# senseBox-MCU_v10.net
KiCad netlist of a schematic drawn in EAGLE
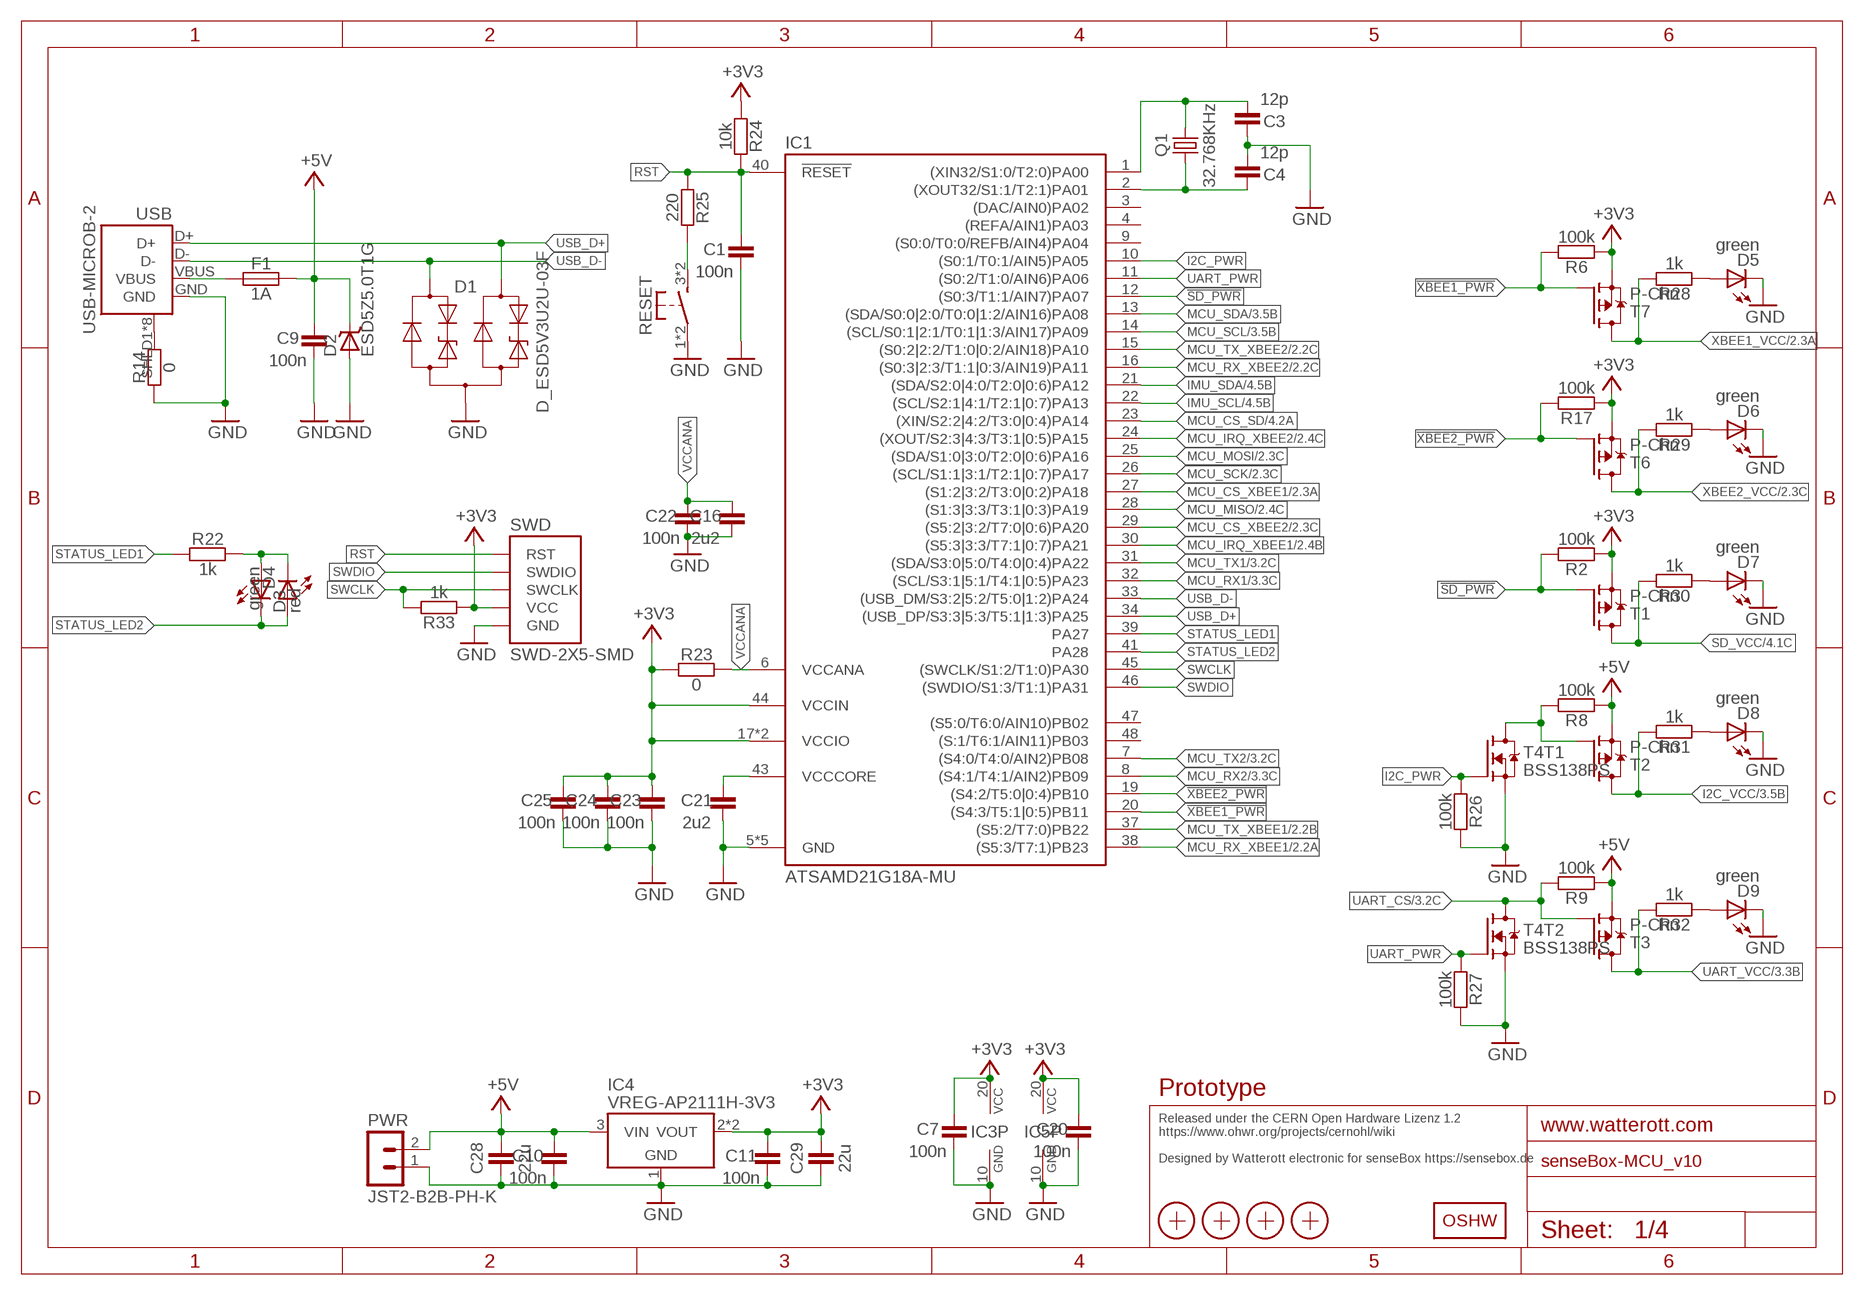
[diagram p0: schematic, sheet 1]
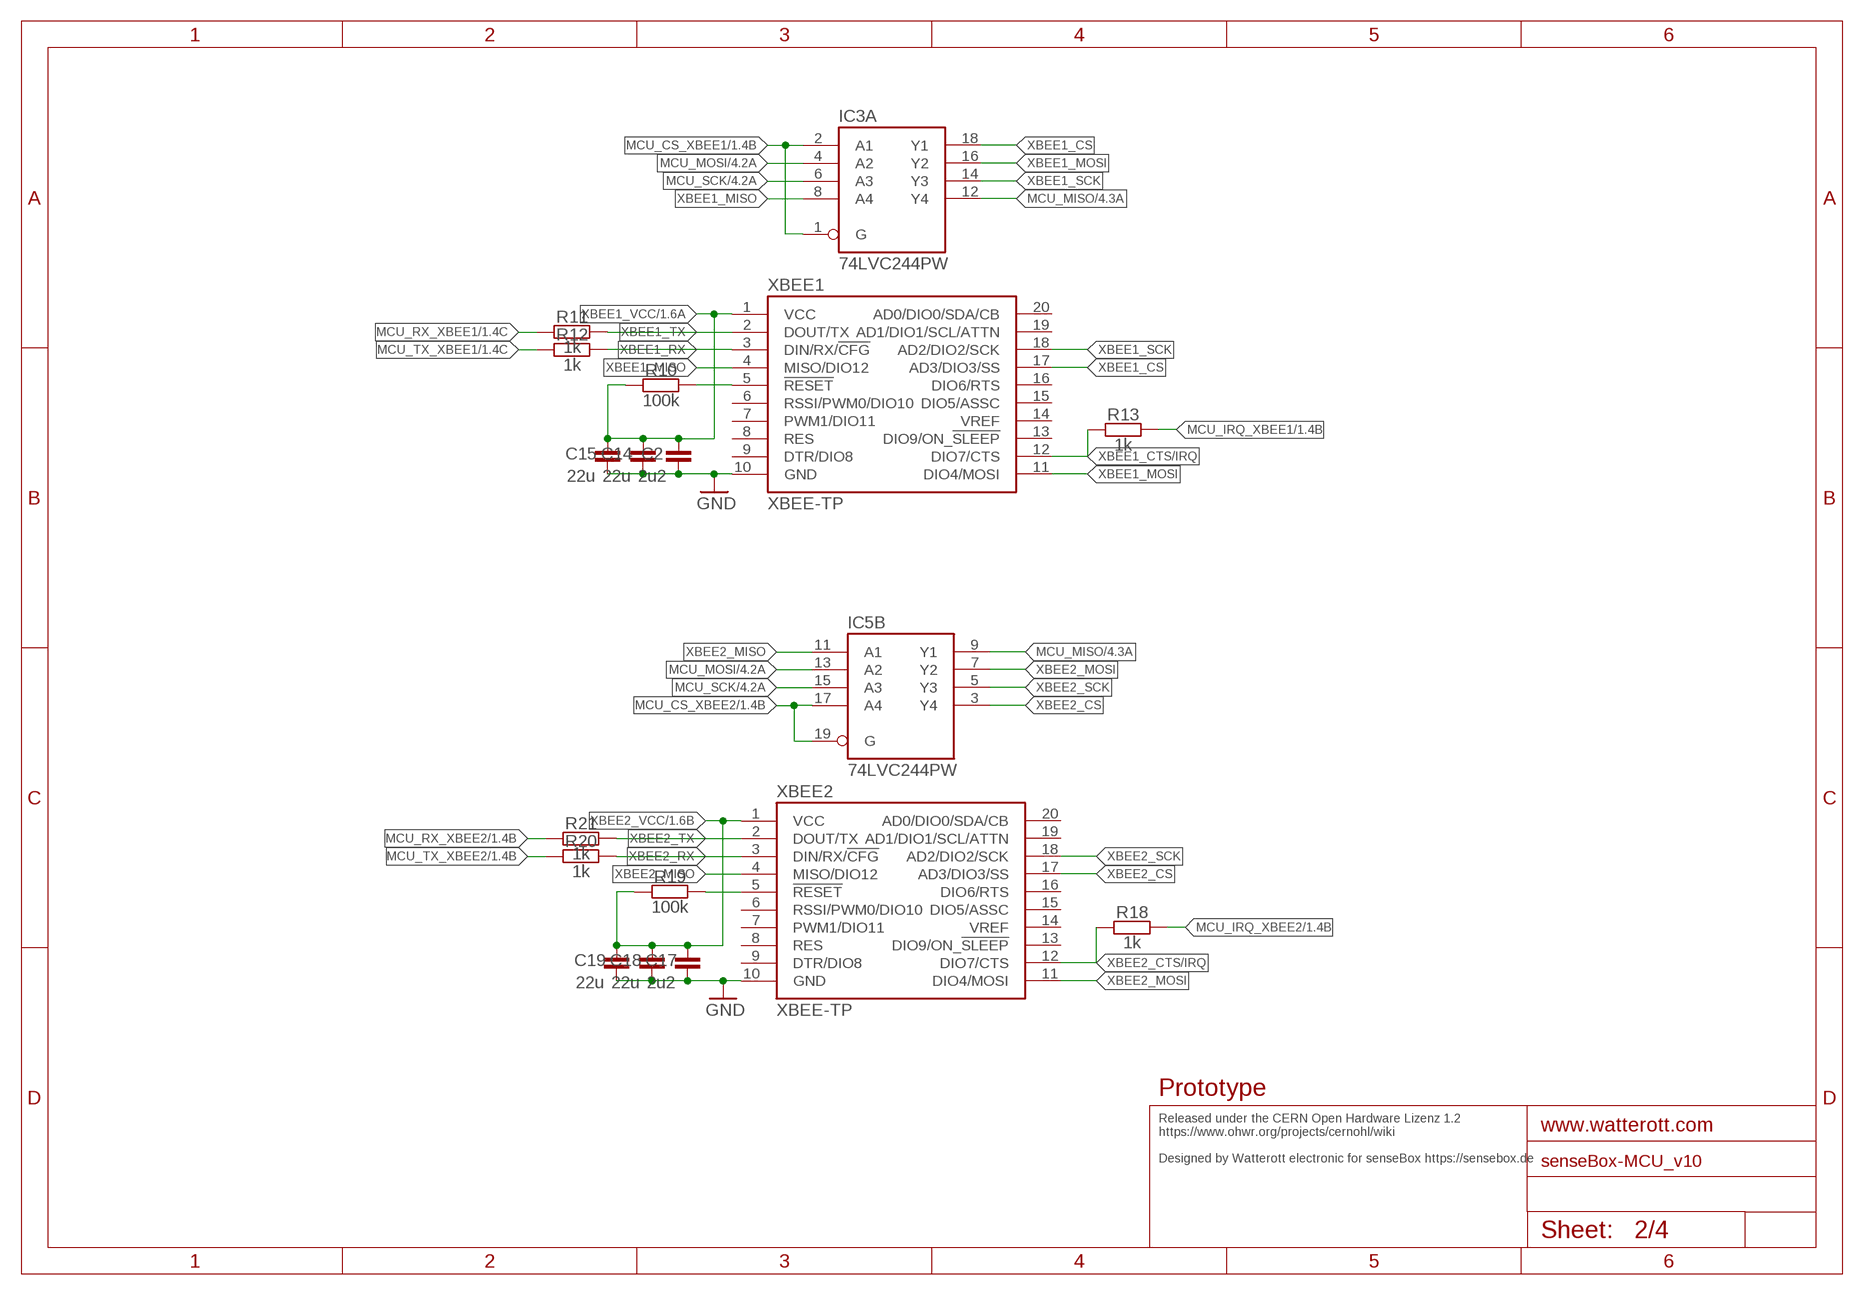
[diagram p1: schematic, sheet 2]
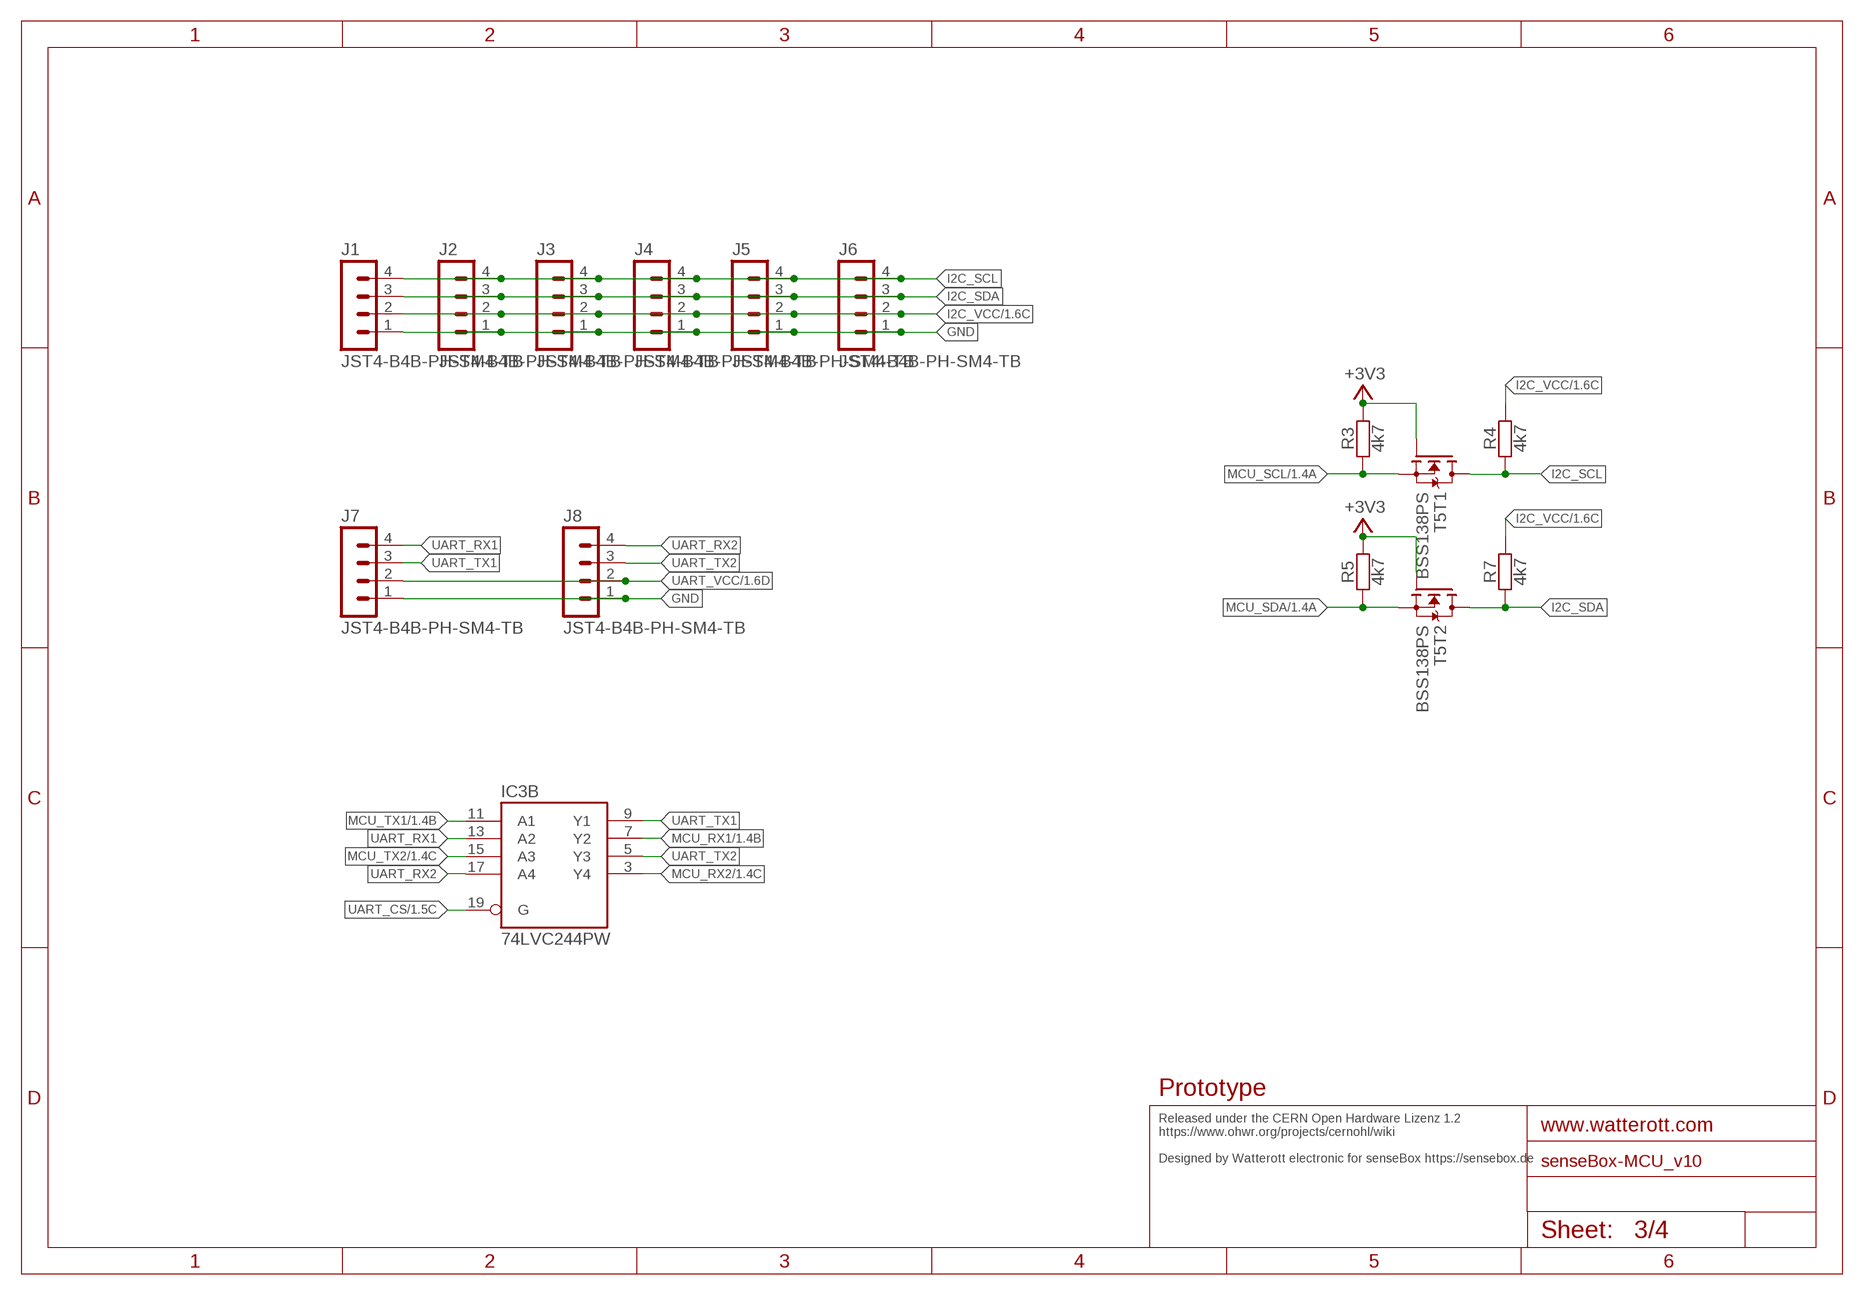
[diagram p2: schematic, sheet 3]
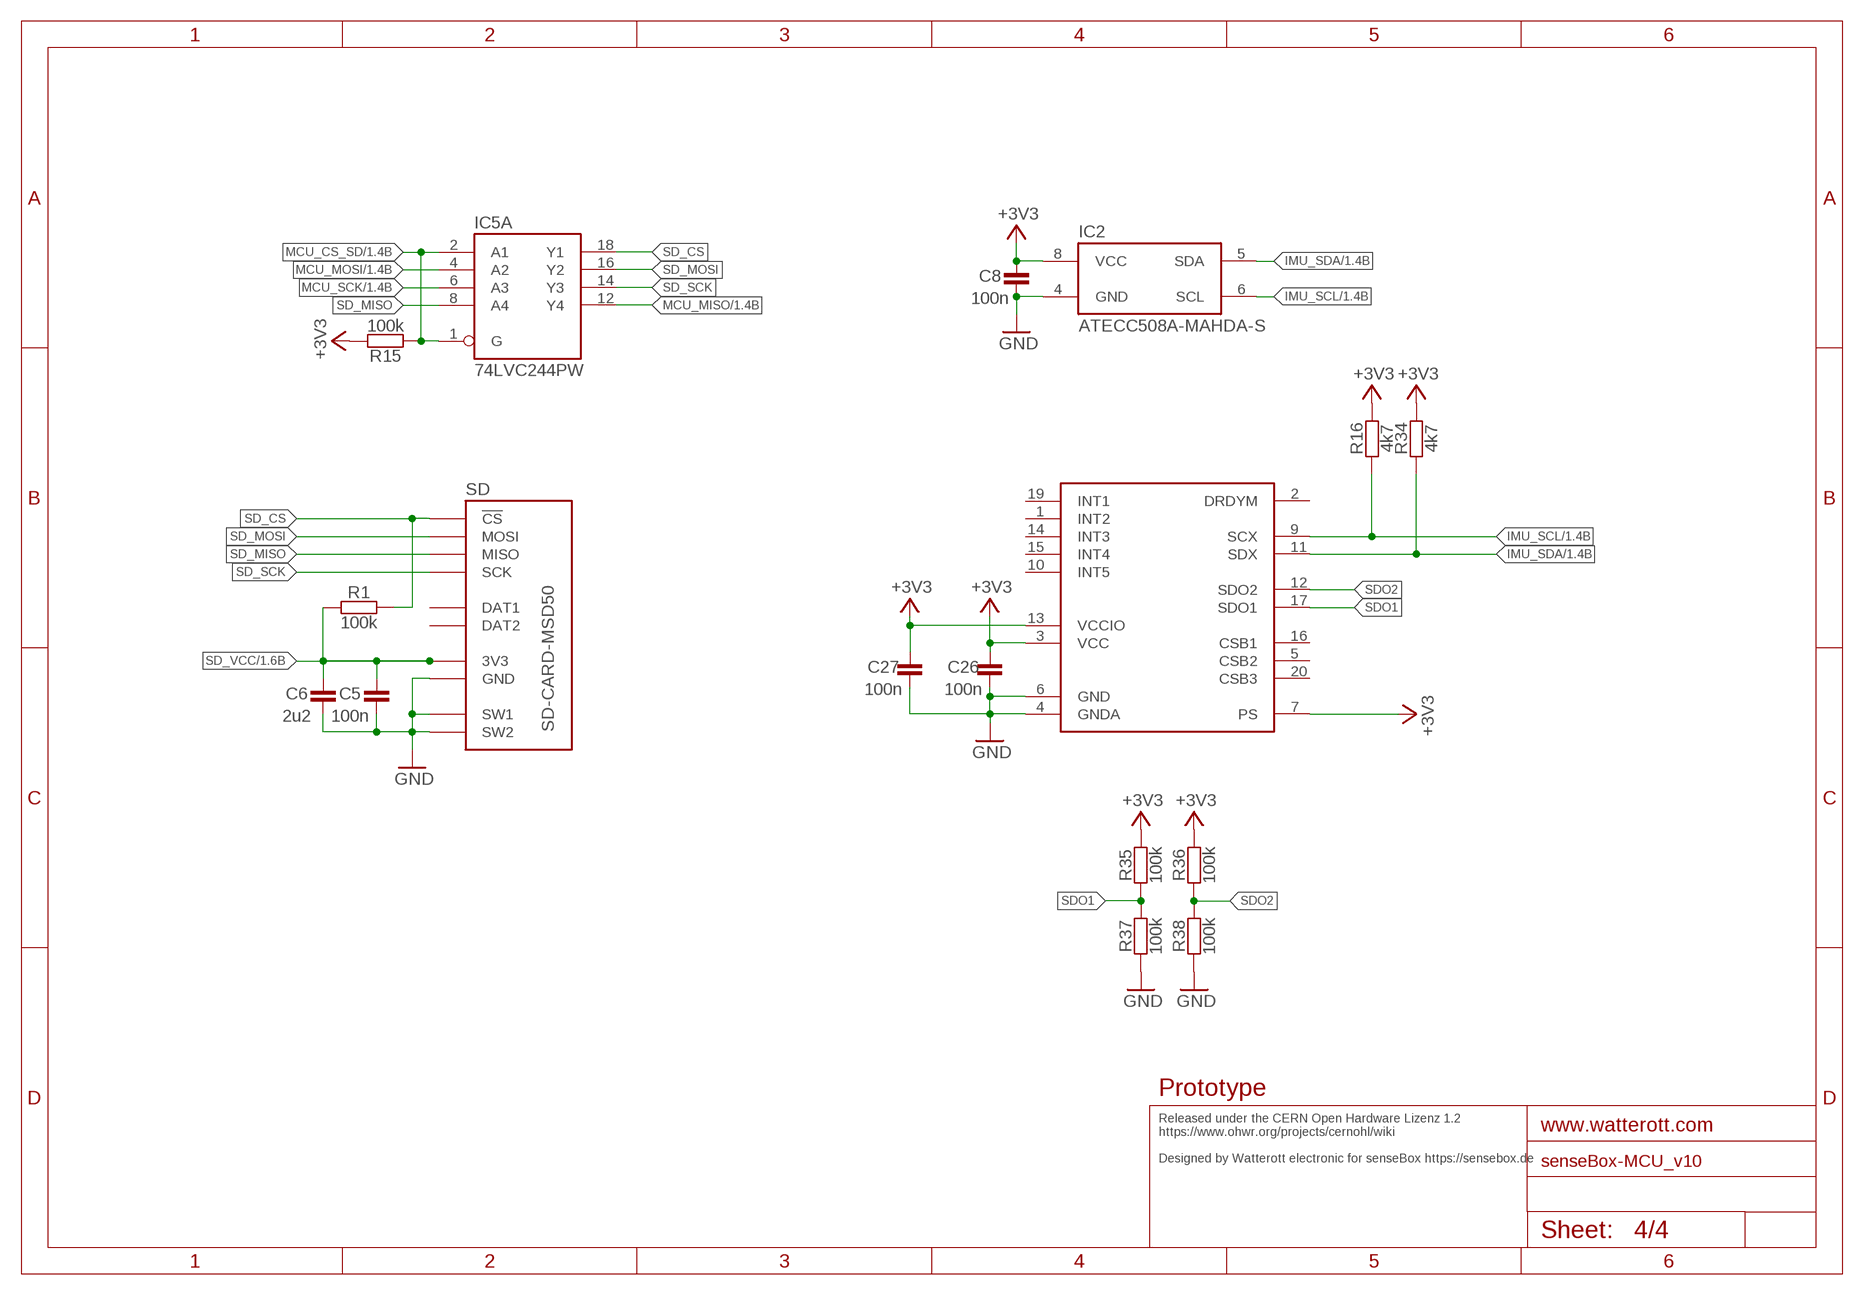
[diagram p3: schematic, sheet 4]

(export (version "E")
  (design (tool "Eeschema 10.0.6"))
  (components
    (comp (ref "C2")
      (value "2u2")
      (footprint "eagle-import:C0402")
      (libsource (lib "eagle-import") (part "CAPACITOR-0402"))
    )
    (comp (ref "C14")
      (value "22u")
      (footprint "eagle-import:C0805")
      (libsource (lib "eagle-import") (part "CAPACITOR-0805"))
    )
    (comp (ref "C15")
      (value "22u")
      (footprint "eagle-import:C0805")
      (libsource (lib "eagle-import") (part "CAPACITOR-0805"))
    )
    (comp (ref "C17")
      (value "2u2")
      (footprint "eagle-import:C0402")
      (libsource (lib "eagle-import") (part "CAPACITOR-0402"))
    )
    (comp (ref "C18")
      (value "22u")
      (footprint "eagle-import:C0805")
      (libsource (lib "eagle-import") (part "CAPACITOR-0805"))
    )
    (comp (ref "C19")
      (value "22u")
      (footprint "eagle-import:C0805")
      (libsource (lib "eagle-import") (part "CAPACITOR-0805"))
    )
    (comp (ref "IC3")
      (value "74LVC244PW")
      (footprint "eagle-import:TSSOP20")
      (libsource (lib "eagle-import") (part "74244PWLVC"))
    )
    (comp (ref "IC5")
      (value "74LVC244PW")
      (footprint "eagle-import:TSSOP20")
      (libsource (lib "eagle-import") (part "74244PWLVC"))
    )
    (comp (ref "R10")
      (value "100k")
      (footprint "eagle-import:C0402")
      (libsource (lib "eagle-import") (part "RESISTOR-0402"))
    )
    (comp (ref "R11")
      (value "1k")
      (footprint "eagle-import:C0402")
      (libsource (lib "eagle-import") (part "RESISTOR-0402"))
    )
    (comp (ref "R12")
      (value "1k")
      (footprint "eagle-import:C0402")
      (libsource (lib "eagle-import") (part "RESISTOR-0402"))
    )
    (comp (ref "R13")
      (value "1k")
      (footprint "eagle-import:C0402")
      (libsource (lib "eagle-import") (part "RESISTOR-0402"))
    )
    (comp (ref "R18")
      (value "1k")
      (footprint "eagle-import:C0402")
      (libsource (lib "eagle-import") (part "RESISTOR-0402"))
    )
    (comp (ref "R19")
      (value "100k")
      (footprint "eagle-import:C0402")
      (libsource (lib "eagle-import") (part "RESISTOR-0402"))
    )
    (comp (ref "R20")
      (value "1k")
      (footprint "eagle-import:C0402")
      (libsource (lib "eagle-import") (part "RESISTOR-0402"))
    )
    (comp (ref "R21")
      (value "1k")
      (footprint "eagle-import:C0402")
      (libsource (lib "eagle-import") (part "RESISTOR-0402"))
    )
    (comp (ref "XBEE1")
      (value "XBEE-TP")
      (footprint "eagle-import:XBEE_TP")
      (libsource (lib "eagle-import") (part "XBEE-TP"))
    )
    (comp (ref "XBEE2")
      (value "XBEE-TP")
      (footprint "eagle-import:XBEE_TP")
      (libsource (lib "eagle-import") (part "XBEE-TP"))
    )
    (comp (ref "C5")
      (value "100n")
      (footprint "eagle-import:C0402")
      (libsource (lib "eagle-import") (part "CAPACITOR-0402"))
    )
    (comp (ref "C6")
      (value "2u2")
      (footprint "eagle-import:C0402")
      (libsource (lib "eagle-import") (part "CAPACITOR-0402"))
    )
    (comp (ref "C8")
      (value "100n")
      (footprint "eagle-import:C0402")
      (libsource (lib "eagle-import") (part "CAPACITOR-0402"))
    )
    (comp (ref "C26")
      (value "100n")
      (footprint "eagle-import:C0402")
      (libsource (lib "eagle-import") (part "CAPACITOR-0402"))
    )
    (comp (ref "C27")
      (value "100n")
      (footprint "eagle-import:C0402")
      (libsource (lib "eagle-import") (part "CAPACITOR-0402"))
    )
    (comp (ref "IC2")
      (value "ATECC508A-MAHDA-S")
      (footprint "eagle-import:UDFN8")
      (libsource (lib "eagle-import") (part "ATECC508A-MAHDA-S"))
    )
    (comp (ref "R1")
      (value "100k")
      (footprint "eagle-import:C0402")
      (libsource (lib "eagle-import") (part "RESISTOR-0402"))
    )
    (comp (ref "R15")
      (value "100k")
      (footprint "eagle-import:C0402")
      (libsource (lib "eagle-import") (part "RESISTOR-0402"))
    )
    (comp (ref "R16")
      (value "4k7")
      (footprint "eagle-import:C0402")
      (libsource (lib "eagle-import") (part "RESISTOR-0402"))
    )
    (comp (ref "R34")
      (value "4k7")
      (footprint "eagle-import:C0402")
      (libsource (lib "eagle-import") (part "RESISTOR-0402"))
    )
    (comp (ref "R35")
      (value "100k")
      (footprint "eagle-import:C0402")
      (libsource (lib "eagle-import") (part "RESISTOR-0402"))
    )
    (comp (ref "R36")
      (value "100k")
      (footprint "eagle-import:C0402")
      (libsource (lib "eagle-import") (part "RESISTOR-0402"))
    )
    (comp (ref "R37")
      (value "100k")
      (footprint "eagle-import:C0402")
      (libsource (lib "eagle-import") (part "RESISTOR-0402"))
    )
    (comp (ref "R38")
      (value "100k")
      (footprint "eagle-import:C0402")
      (libsource (lib "eagle-import") (part "RESISTOR-0402"))
    )
    (comp (ref "SD")
      (value "SD-CARD-MSD50")
      (footprint "eagle-import:SD_5031821853")
      (libsource (lib "eagle-import") (part "SD-CARD-MSD50"))
    )
    (comp (ref "U1")
      (value "BMX055")
      (footprint "eagle-import:BMX055")
      (libsource (lib "eagle-import") (part "BMX055"))
    )
    (comp (ref "C1")
      (value "100n")
      (footprint "eagle-import:C0402")
      (libsource (lib "eagle-import") (part "CAPACITOR-0402"))
    )
    (comp (ref "C3")
      (value "12p")
      (footprint "eagle-import:C0402")
      (libsource (lib "eagle-import") (part "CAPACITOR-0402"))
    )
    (comp (ref "C4")
      (value "12p")
      (footprint "eagle-import:C0402")
      (libsource (lib "eagle-import") (part "CAPACITOR-0402"))
    )
    (comp (ref "C7")
      (value "100n")
      (footprint "eagle-import:C0402")
      (libsource (lib "eagle-import") (part "CAPACITOR-0402"))
    )
    (comp (ref "C9")
      (value "100n")
      (footprint "eagle-import:C0402")
      (libsource (lib "eagle-import") (part "CAPACITOR-0402"))
    )
    (comp (ref "C10")
      (value "100n")
      (footprint "eagle-import:C0402")
      (libsource (lib "eagle-import") (part "CAPACITOR-0402"))
    )
    (comp (ref "C11")
      (value "100n")
      (footprint "eagle-import:C0402")
      (libsource (lib "eagle-import") (part "CAPACITOR-0402"))
    )
    (comp (ref "C16")
      (value "2u2")
      (footprint "eagle-import:C0402")
      (libsource (lib "eagle-import") (part "CAPACITOR-0402"))
    )
    (comp (ref "C20")
      (value "100n")
      (footprint "eagle-import:C0402")
      (libsource (lib "eagle-import") (part "CAPACITOR-0402"))
    )
    (comp (ref "C21")
      (value "2u2")
      (footprint "eagle-import:C0402")
      (libsource (lib "eagle-import") (part "CAPACITOR-0402"))
    )
    (comp (ref "C22")
      (value "100n")
      (footprint "eagle-import:C0402")
      (libsource (lib "eagle-import") (part "CAPACITOR-0402"))
    )
    (comp (ref "C23")
      (value "100n")
      (footprint "eagle-import:C0402")
      (libsource (lib "eagle-import") (part "CAPACITOR-0402"))
    )
    (comp (ref "C24")
      (value "100n")
      (footprint "eagle-import:C0402")
      (libsource (lib "eagle-import") (part "CAPACITOR-0402"))
    )
    (comp (ref "C25")
      (value "100n")
      (footprint "eagle-import:C0402")
      (libsource (lib "eagle-import") (part "CAPACITOR-0402"))
    )
    (comp (ref "C28")
      (value "22u")
      (footprint "eagle-import:C0805")
      (libsource (lib "eagle-import") (part "CAPACITOR-0805"))
    )
    (comp (ref "C29")
      (value "22u")
      (footprint "eagle-import:C0805")
      (libsource (lib "eagle-import") (part "CAPACITOR-0805"))
    )
    (comp (ref "D1")
      (value "D_ESD5V3U2U-03F")
      (footprint "eagle-import:SOT723")
      (libsource (lib "eagle-import") (part "D_ESD5V3U2U-03F"))
    )
    (comp (ref "D2")
      (value "ESD5Z5.0T1G")
      (footprint "eagle-import:SOD523")
      (libsource (lib "eagle-import") (part "D_TVS-SOD523"))
    )
    (comp (ref "D3")
      (value "red")
      (footprint "eagle-import:C0603")
      (libsource (lib "eagle-import") (part "LED-0603"))
    )
    (comp (ref "D4")
      (value "green")
      (footprint "eagle-import:C0603")
      (libsource (lib "eagle-import") (part "LED-0603"))
    )
    (comp (ref "D5")
      (value "green")
      (footprint "eagle-import:C0603")
      (libsource (lib "eagle-import") (part "LED-0603"))
    )
    (comp (ref "D6")
      (value "green")
      (footprint "eagle-import:C0603")
      (libsource (lib "eagle-import") (part "LED-0603"))
    )
    (comp (ref "D7")
      (value "green")
      (footprint "eagle-import:C0603")
      (libsource (lib "eagle-import") (part "LED-0603"))
    )
    (comp (ref "D8")
      (value "green")
      (footprint "eagle-import:C0603")
      (libsource (lib "eagle-import") (part "LED-0603"))
    )
    (comp (ref "D9")
      (value "green")
      (footprint "eagle-import:C0603")
      (libsource (lib "eagle-import") (part "LED-0603"))
    )
    (comp (ref "F1")
      (value "1A")
      (footprint "eagle-import:C0805")
      (libsource (lib "eagle-import") (part "FUSE-0805"))
    )
    (comp (ref "IC1")
      (value "ATSAMD21G18A-MU")
      (footprint "eagle-import:QFN48-PAD")
      (libsource (lib "eagle-import") (part "ATSAMD21G18A-MU"))
    )
    (comp (ref "IC4")
      (value "VREG-AP2111H-3V3")
      (footprint "eagle-import:SOT223")
      (libsource (lib "eagle-import") (part "VREG-TS1117CW-3V3"))
    )
    (comp (ref "LOGO2")
      (value "OSHW_LOGOX0070")
      (footprint "eagle-import:OSHW_6X70")
      (libsource (lib "eagle-import") (part "OSHW_LOGOX0070"))
    )
    (comp (ref "PWR")
      (value "JST2-B2B-PH-K")
      (footprint "eagle-import:JST_B2B-PH-K")
      (libsource (lib "eagle-import") (part "JST2-B2B-PH-K"))
    )
    (comp (ref "Q1")
      (value "32.768KHz")
      (footprint "eagle-import:CRYSTAL_ZM315")
      (libsource (lib "eagle-import") (part "CRYSTAL-ZM315"))
    )
    (comp (ref "R2")
      (value "100k")
      (footprint "eagle-import:C0402")
      (libsource (lib "eagle-import") (part "RESISTOR-0402"))
    )
    (comp (ref "R6")
      (value "100k")
      (footprint "eagle-import:C0402")
      (libsource (lib "eagle-import") (part "RESISTOR-0402"))
    )
    (comp (ref "R8")
      (value "100k")
      (footprint "eagle-import:C0402")
      (libsource (lib "eagle-import") (part "RESISTOR-0402"))
    )
    (comp (ref "R9")
      (value "100k")
      (footprint "eagle-import:C0402")
      (libsource (lib "eagle-import") (part "RESISTOR-0402"))
    )
    (comp (ref "R14")
      (value "0")
      (footprint "eagle-import:C0402")
      (libsource (lib "eagle-import") (part "RESISTOR-0402"))
    )
    (comp (ref "R17")
      (value "100k")
      (footprint "eagle-import:C0402")
      (libsource (lib "eagle-import") (part "RESISTOR-0402"))
    )
    (comp (ref "R22")
      (value "1k")
      (footprint "eagle-import:C0402")
      (libsource (lib "eagle-import") (part "RESISTOR-0402"))
    )
    (comp (ref "R23")
      (value "0")
      (footprint "eagle-import:C0402")
      (libsource (lib "eagle-import") (part "RESISTOR-0402"))
    )
    (comp (ref "R24")
      (value "10k")
      (footprint "eagle-import:C0402")
      (libsource (lib "eagle-import") (part "RESISTOR-0402"))
    )
    (comp (ref "R25")
      (value "220")
      (footprint "eagle-import:C0402")
      (libsource (lib "eagle-import") (part "RESISTOR-0402"))
    )
    (comp (ref "R26")
      (value "100k")
      (footprint "eagle-import:C0402")
      (libsource (lib "eagle-import") (part "RESISTOR-0402"))
    )
    (comp (ref "R27")
      (value "100k")
      (footprint "eagle-import:C0402")
      (libsource (lib "eagle-import") (part "RESISTOR-0402"))
    )
    (comp (ref "R28")
      (value "1k")
      (footprint "eagle-import:C0402")
      (libsource (lib "eagle-import") (part "RESISTOR-0402"))
    )
    (comp (ref "R29")
      (value "1k")
      (footprint "eagle-import:C0402")
      (libsource (lib "eagle-import") (part "RESISTOR-0402"))
    )
    (comp (ref "R30")
      (value "1k")
      (footprint "eagle-import:C0402")
      (libsource (lib "eagle-import") (part "RESISTOR-0402"))
    )
    (comp (ref "R31")
      (value "1k")
      (footprint "eagle-import:C0402")
      (libsource (lib "eagle-import") (part "RESISTOR-0402"))
    )
    (comp (ref "R32")
      (value "1k")
      (footprint "eagle-import:C0402")
      (libsource (lib "eagle-import") (part "RESISTOR-0402"))
    )
    (comp (ref "R33")
      (value "1k")
      (footprint "eagle-import:C0402")
      (libsource (lib "eagle-import") (part "RESISTOR-0402"))
    )
    (comp (ref "RESET")
      (value "SW-TACTILE-PTS840P")
      (footprint "eagle-import:PTS840P")
      (libsource (lib "eagle-import") (part "SW-TACTILE-PTS840P"))
    )
    (comp (ref "SWD")
      (value "SWD-2X5-SMD")
      (footprint "eagle-import:SWD-2X5_SMD")
      (libsource (lib "eagle-import") (part "SWD-2X5-SMD"))
    )
    (comp (ref "T1")
      (value "P-Chn")
      (footprint "eagle-import:SOT23")
      (libsource (lib "eagle-import") (part "MOSFET-P-SOT23"))
    )
    (comp (ref "T2")
      (value "P-Chn")
      (footprint "eagle-import:SOT23")
      (libsource (lib "eagle-import") (part "MOSFET-P-SOT23"))
    )
    (comp (ref "T3")
      (value "P-Chn")
      (footprint "eagle-import:SOT23")
      (libsource (lib "eagle-import") (part "MOSFET-P-SOT23"))
    )
    (comp (ref "T4")
      (value "BSS138PS")
      (footprint "eagle-import:SOT363")
      (libsource (lib "eagle-import") (part "BSS138PS"))
    )
    (comp (ref "T6")
      (value "P-Chn")
      (footprint "eagle-import:SOT23")
      (libsource (lib "eagle-import") (part "MOSFET-P-SOT23"))
    )
    (comp (ref "T7")
      (value "P-Chn")
      (footprint "eagle-import:SOT23")
      (libsource (lib "eagle-import") (part "MOSFET-P-SOT23"))
    )
    (comp (ref "USB")
      (value "USB-MICROB-2")
      (footprint "eagle-import:USB-MICROB-10118194")
      (libsource (lib "eagle-import") (part "USB-MICROB-2"))
    )
    (comp (ref "X1")
      (value "PASSER-07")
      (footprint "eagle-import:PASSER_07MM")
      (libsource (lib "eagle-import") (part "PASSER-07"))
    )
    (comp (ref "X2")
      (value "PASSER-07")
      (footprint "eagle-import:PASSER_07MM")
      (libsource (lib "eagle-import") (part "PASSER-07"))
    )
    (comp (ref "X3")
      (value "PASSER-07")
      (footprint "eagle-import:PASSER_07MM")
      (libsource (lib "eagle-import") (part "PASSER-07"))
    )
    (comp (ref "X4")
      (value "PASSER-07")
      (footprint "eagle-import:PASSER_07MM")
      (libsource (lib "eagle-import") (part "PASSER-07"))
    )
    (comp (ref "J1")
      (value "JST4-B4B-PH-SM4-TB")
      (footprint "eagle-import:JST_B4B-PH-SM4-TB")
      (libsource (lib "eagle-import") (part "JST4-B4B-PH-SM4-TB"))
    )
    (comp (ref "J2")
      (value "JST4-B4B-PH-SM4-TB")
      (footprint "eagle-import:JST_B4B-PH-SM4-TB")
      (libsource (lib "eagle-import") (part "JST4-B4B-PH-SM4-TB"))
    )
    (comp (ref "J3")
      (value "JST4-B4B-PH-SM4-TB")
      (footprint "eagle-import:JST_B4B-PH-SM4-TB")
      (libsource (lib "eagle-import") (part "JST4-B4B-PH-SM4-TB"))
    )
    (comp (ref "J4")
      (value "JST4-B4B-PH-SM4-TB")
      (footprint "eagle-import:JST_B4B-PH-SM4-TB")
      (libsource (lib "eagle-import") (part "JST4-B4B-PH-SM4-TB"))
    )
    (comp (ref "J5")
      (value "JST4-B4B-PH-SM4-TB")
      (footprint "eagle-import:JST_B4B-PH-SM4-TB")
      (libsource (lib "eagle-import") (part "JST4-B4B-PH-SM4-TB"))
    )
    (comp (ref "J6")
      (value "JST4-B4B-PH-SM4-TB")
      (footprint "eagle-import:JST_B4B-PH-SM4-TB")
      (libsource (lib "eagle-import") (part "JST4-B4B-PH-SM4-TB"))
    )
    (comp (ref "J7")
      (value "JST4-B4B-PH-SM4-TB")
      (footprint "eagle-import:JST_B4B-PH-SM4-TB")
      (libsource (lib "eagle-import") (part "JST4-B4B-PH-SM4-TB"))
    )
    (comp (ref "J8")
      (value "JST4-B4B-PH-SM4-TB")
      (footprint "eagle-import:JST_B4B-PH-SM4-TB")
      (libsource (lib "eagle-import") (part "JST4-B4B-PH-SM4-TB"))
    )
    (comp (ref "R3")
      (value "4k7")
      (footprint "eagle-import:C0402")
      (libsource (lib "eagle-import") (part "RESISTOR-0402"))
    )
    (comp (ref "R4")
      (value "4k7")
      (footprint "eagle-import:C0402")
      (libsource (lib "eagle-import") (part "RESISTOR-0402"))
    )
    (comp (ref "R5")
      (value "4k7")
      (footprint "eagle-import:C0402")
      (libsource (lib "eagle-import") (part "RESISTOR-0402"))
    )
    (comp (ref "R7")
      (value "4k7")
      (footprint "eagle-import:C0402")
      (libsource (lib "eagle-import") (part "RESISTOR-0402"))
    )
    (comp (ref "T5")
      (value "BSS138PS")
      (footprint "eagle-import:SOT363")
      (libsource (lib "eagle-import") (part "BSS138PS"))
    )
  )
  (nets
    (net (code "1") (name "+3V3") (class "Default")
      (node (ref "C11") (pin "2") (pinfunction "2_2") (pintype "passive"))
      (node (ref "C20") (pin "2") (pinfunction "2_2") (pintype "passive"))
      (node (ref "C23") (pin "2") (pinfunction "2_2") (pintype "passive"))
      (node (ref "C24") (pin "2") (pinfunction "2_2") (pintype "passive"))
      (node (ref "C25") (pin "2") (pinfunction "2_2") (pintype "passive"))
      (node (ref "C26") (pin "2") (pinfunction "2_2") (pintype "passive"))
      (node (ref "C27") (pin "2") (pinfunction "2_2") (pintype "passive"))
      (node (ref "C29") (pin "2") (pinfunction "2_2") (pintype "passive"))
      (node (ref "C7") (pin "2") (pinfunction "2_2") (pintype "passive"))
      (node (ref "C8") (pin "2") (pinfunction "2_2") (pintype "passive"))
      (node (ref "IC1") (pin "17") (pinfunction "VCCIO_17") (pintype "power_in"))
      (node (ref "IC1") (pin "36") (pinfunction "VCCIO_36") (pintype "power_in"))
      (node (ref "IC1") (pin "44") (pinfunction "VCCIN_44") (pintype "power_in"))
      (node (ref "IC2") (pin "8") (pinfunction "VCC_8") (pintype "power_in"))
      (node (ref "IC3") (pin "20") (pinfunction "VCC_20") (pintype "power_in"))
      (node (ref "IC4") (pin "2") (pinfunction "VOUT_2") (pintype "power_in"))
      (node (ref "IC4") (pin "4") (pinfunction "VOUT_4") (pintype "power_in"))
      (node (ref "IC5") (pin "20") (pinfunction "VCC_20") (pintype "power_in"))
      (node (ref "R15") (pin "2") (pinfunction "2_2") (pintype "passive"))
      (node (ref "R16") (pin "2") (pinfunction "2_2") (pintype "passive"))
      (node (ref "R17") (pin "1") (pinfunction "1_1") (pintype "passive"))
      (node (ref "R2") (pin "1") (pinfunction "1_1") (pintype "passive"))
      (node (ref "R23") (pin "1") (pinfunction "1_1") (pintype "passive"))
      (node (ref "R24") (pin "1") (pinfunction "1_1") (pintype "passive"))
      (node (ref "R3") (pin "2") (pinfunction "2_2") (pintype "passive"))
      (node (ref "R33") (pin "1") (pinfunction "1_1") (pintype "passive"))
      (node (ref "R34") (pin "2") (pinfunction "2_2") (pintype "passive"))
      (node (ref "R35") (pin "2") (pinfunction "2_2") (pintype "passive"))
      (node (ref "R36") (pin "2") (pinfunction "2_2") (pintype "passive"))
      (node (ref "R5") (pin "2") (pinfunction "2_2") (pintype "passive"))
      (node (ref "R6") (pin "1") (pinfunction "1_1") (pintype "passive"))
      (node (ref "SWD") (pin "VCC") (pinfunction "VCC_VCC") (pintype "power_in"))
      (node (ref "T1") (pin "2") (pinfunction "S_2") (pintype "passive"))
      (node (ref "T5") (pin "2") (pinfunction "G_2") (pintype "passive"))
      (node (ref "T5") (pin "5") (pinfunction "G_5") (pintype "passive"))
      (node (ref "T6") (pin "2") (pinfunction "S_2") (pintype "passive"))
      (node (ref "T7") (pin "2") (pinfunction "S_2") (pintype "passive"))
      (node (ref "U1") (pin "13") (pinfunction "VCCIO_13") (pintype "bidirectional"))
      (node (ref "U1") (pin "3") (pinfunction "VCC_3") (pintype "power_in"))
      (node (ref "U1") (pin "7") (pinfunction "PS_7") (pintype "bidirectional"))
    )
    (net (code "2") (name "+5V") (class "Default")
      (node (ref "C10") (pin "2") (pinfunction "2_2") (pintype "passive"))
      (node (ref "C28") (pin "2") (pinfunction "2_2") (pintype "passive"))
      (node (ref "C9") (pin "2") (pinfunction "2_2") (pintype "passive"))
      (node (ref "D2") (pin "C") (pinfunction "C_C") (pintype "passive"))
      (node (ref "F1") (pin "2") (pinfunction "2_2") (pintype "passive"))
      (node (ref "IC4") (pin "3") (pinfunction "VIN_3") (pintype "power_in"))
      (node (ref "PWR") (pin "2") (pinfunction "2_2") (pintype "passive"))
      (node (ref "R8") (pin "1") (pinfunction "1_1") (pintype "passive"))
      (node (ref "R9") (pin "1") (pinfunction "1_1") (pintype "passive"))
      (node (ref "T2") (pin "2") (pinfunction "S_2") (pintype "passive"))
      (node (ref "T3") (pin "2") (pinfunction "S_2") (pintype "passive"))
    )
    (net (code "3") (name "GND") (class "Default")
      (node (ref "C1") (pin "1") (pinfunction "1_1") (pintype "passive"))
      (node (ref "C10") (pin "1") (pinfunction "1_1") (pintype "passive"))
      (node (ref "C11") (pin "1") (pinfunction "1_1") (pintype "passive"))
      (node (ref "C14") (pin "1") (pinfunction "1_1") (pintype "passive"))
      (node (ref "C15") (pin "1") (pinfunction "1_1") (pintype "passive"))
      (node (ref "C16") (pin "1") (pinfunction "1_1") (pintype "passive"))
      (node (ref "C17") (pin "1") (pinfunction "1_1") (pintype "passive"))
      (node (ref "C18") (pin "1") (pinfunction "1_1") (pintype "passive"))
      (node (ref "C19") (pin "1") (pinfunction "1_1") (pintype "passive"))
      (node (ref "C2") (pin "1") (pinfunction "1_1") (pintype "passive"))
      (node (ref "C20") (pin "1") (pinfunction "1_1") (pintype "passive"))
      (node (ref "C21") (pin "1") (pinfunction "1_1") (pintype "passive"))
      (node (ref "C22") (pin "1") (pinfunction "1_1") (pintype "passive"))
      (node (ref "C23") (pin "1") (pinfunction "1_1") (pintype "passive"))
      (node (ref "C24") (pin "1") (pinfunction "1_1") (pintype "passive"))
      (node (ref "C25") (pin "1") (pinfunction "1_1") (pintype "passive"))
      (node (ref "C26") (pin "1") (pinfunction "1_1") (pintype "passive"))
      (node (ref "C27") (pin "1") (pinfunction "1_1") (pintype "passive"))
      (node (ref "C28") (pin "1") (pinfunction "1_1") (pintype "passive"))
      (node (ref "C29") (pin "1") (pinfunction "1_1") (pintype "passive"))
      (node (ref "C3") (pin "2") (pinfunction "2_2") (pintype "passive"))
      (node (ref "C4") (pin "1") (pinfunction "1_1") (pintype "passive"))
      (node (ref "C5") (pin "1") (pinfunction "1_1") (pintype "passive"))
      (node (ref "C6") (pin "1") (pinfunction "1_1") (pintype "passive"))
      (node (ref "C7") (pin "1") (pinfunction "1_1") (pintype "passive"))
      (node (ref "C8") (pin "1") (pinfunction "1_1") (pintype "passive"))
      (node (ref "C9") (pin "1") (pinfunction "1_1") (pintype "passive"))
      (node (ref "D1") (pin "3") (pinfunction "A_3") (pintype "passive"))
      (node (ref "D2") (pin "A") (pinfunction "A_A") (pintype "passive"))
      (node (ref "D5") (pin "C") (pinfunction "C_C") (pintype "passive"))
      (node (ref "D6") (pin "C") (pinfunction "C_C") (pintype "passive"))
      (node (ref "D7") (pin "C") (pinfunction "C_C") (pintype "passive"))
      (node (ref "D8") (pin "C") (pinfunction "C_C") (pintype "passive"))
      (node (ref "D9") (pin "C") (pinfunction "C_C") (pintype "passive"))
      (node (ref "IC1") (pin "18") (pinfunction "GND_18") (pintype "power_in"))
      (node (ref "IC1") (pin "35") (pinfunction "GND_35") (pintype "power_in"))
      (node (ref "IC1") (pin "42") (pinfunction "GND_42") (pintype "power_in"))
      (node (ref "IC1") (pin "5") (pinfunction "GND_5") (pintype "power_in"))
      (node (ref "IC1") (pin "TP") (pinfunction "GND_TP") (pintype "power_in"))
      (node (ref "IC2") (pin "4") (pinfunction "GND_4") (pintype "power_in"))
      (node (ref "IC3") (pin "10") (pinfunction "GND_10") (pintype "power_in"))
      (node (ref "IC4") (pin "1") (pinfunction "GND_1") (pintype "power_in"))
      (node (ref "IC5") (pin "10") (pinfunction "GND_10") (pintype "power_in"))
      (node (ref "J1") (pin "1") (pinfunction "1_1") (pintype "passive"))
      (node (ref "J2") (pin "1") (pinfunction "1_1") (pintype "passive"))
      (node (ref "J3") (pin "1") (pinfunction "1_1") (pintype "passive"))
      (node (ref "J4") (pin "1") (pinfunction "1_1") (pintype "passive"))
      (node (ref "J5") (pin "1") (pinfunction "1_1") (pintype "passive"))
      (node (ref "J6") (pin "1") (pinfunction "1_1") (pintype "passive"))
      (node (ref "J7") (pin "1") (pinfunction "1_1") (pintype "passive"))
      (node (ref "J8") (pin "1") (pinfunction "1_1") (pintype "passive"))
      (node (ref "PWR") (pin "1") (pinfunction "1_1") (pintype "passive"))
      (node (ref "R14") (pin "1") (pinfunction "1_1") (pintype "passive"))
      (node (ref "R26") (pin "2") (pinfunction "2_2") (pintype "passive"))
      (node (ref "R27") (pin "2") (pinfunction "2_2") (pintype "passive"))
      (node (ref "R37") (pin "1") (pinfunction "1_1") (pintype "passive"))
      (node (ref "R38") (pin "1") (pinfunction "1_1") (pintype "passive"))
      (node (ref "RESET") (pin "1") (pinfunction "P1_1") (pintype "passive"))
      (node (ref "RESET") (pin "2") (pinfunction "P1_2") (pintype "passive"))
      (node (ref "SD") (pin "GND") (pinfunction "GND_GND") (pintype "bidirectional"))
      (node (ref "SD") (pin "SW1") (pinfunction "SW1_SW1") (pintype "bidirectional"))
      (node (ref "SD") (pin "SW2") (pinfunction "SW2_SW2") (pintype "bidirectional"))
      (node (ref "SWD") (pin "GND@1") (pinfunction "GND_GND@1") (pintype "power_in"))
      (node (ref "SWD") (pin "GND@2") (pinfunction "GND_GND@2") (pintype "power_in"))
      (node (ref "SWD") (pin "GND@3") (pinfunction "GND_GND@3") (pintype "power_in"))
      (node (ref "T4") (pin "1") (pinfunction "S_1") (pintype "passive"))
      (node (ref "T4") (pin "4") (pinfunction "S_4") (pintype "passive"))
      (node (ref "U1") (pin "4") (pinfunction "GNDA_4") (pintype "power_in"))
      (node (ref "U1") (pin "6") (pinfunction "GND_6") (pintype "power_in"))
      (node (ref "USB") (pin "GND") (pinfunction "GND_GND") (pintype "power_in"))
      (node (ref "XBEE1") (pin "10") (pinfunction "GND_10") (pintype "power_in"))
      (node (ref "XBEE2") (pin "10") (pinfunction "GND_10") (pintype "power_in"))
    )
    (net (code "4") (name "I2C_PWR") (class "Default")
      (node (ref "IC1") (pin "10") (pinfunction "(S0:1/T0:1/AIN5)PA05_10") (pintype "bidirectional"))
      (node (ref "R26") (pin "1") (pinfunction "1_1") (pintype "passive"))
      (node (ref "T4") (pin "2") (pinfunction "G_2") (pintype "passive"))
    )
    (net (code "5") (name "I2C_SCL") (class "Default")
      (node (ref "J1") (pin "4") (pinfunction "4_4") (pintype "passive"))
      (node (ref "J2") (pin "4") (pinfunction "4_4") (pintype "passive"))
      (node (ref "J3") (pin "4") (pinfunction "4_4") (pintype "passive"))
      (node (ref "J4") (pin "4") (pinfunction "4_4") (pintype "passive"))
      (node (ref "J5") (pin "4") (pinfunction "4_4") (pintype "passive"))
      (node (ref "J6") (pin "4") (pinfunction "4_4") (pintype "passive"))
      (node (ref "R4") (pin "1") (pinfunction "1_1") (pintype "passive"))
      (node (ref "T5") (pin "6") (pinfunction "D_6") (pintype "passive"))
    )
    (net (code "6") (name "I2C_SDA") (class "Default")
      (node (ref "J1") (pin "3") (pinfunction "3_3") (pintype "passive"))
      (node (ref "J2") (pin "3") (pinfunction "3_3") (pintype "passive"))
      (node (ref "J3") (pin "3") (pinfunction "3_3") (pintype "passive"))
      (node (ref "J4") (pin "3") (pinfunction "3_3") (pintype "passive"))
      (node (ref "J5") (pin "3") (pinfunction "3_3") (pintype "passive"))
      (node (ref "J6") (pin "3") (pinfunction "3_3") (pintype "passive"))
      (node (ref "R7") (pin "1") (pinfunction "1_1") (pintype "passive"))
      (node (ref "T5") (pin "3") (pinfunction "D_3") (pintype "passive"))
    )
    (net (code "7") (name "I2C_VCC") (class "Default")
      (node (ref "J1") (pin "2") (pinfunction "2_2") (pintype "passive"))
      (node (ref "J2") (pin "2") (pinfunction "2_2") (pintype "passive"))
      (node (ref "J3") (pin "2") (pinfunction "2_2") (pintype "passive"))
      (node (ref "J4") (pin "2") (pinfunction "2_2") (pintype "passive"))
      (node (ref "J5") (pin "2") (pinfunction "2_2") (pintype "passive"))
      (node (ref "J6") (pin "2") (pinfunction "2_2") (pintype "passive"))
      (node (ref "R31") (pin "2") (pinfunction "2_2") (pintype "passive"))
      (node (ref "R4") (pin "2") (pinfunction "2_2") (pintype "passive"))
      (node (ref "R7") (pin "2") (pinfunction "2_2") (pintype "passive"))
      (node (ref "T2") (pin "3") (pinfunction "D_3") (pintype "passive"))
    )
    (net (code "8") (name "IMU_SCL") (class "Default")
      (node (ref "IC1") (pin "22") (pinfunction "(SCL/S2:1|4:1/T2:1|0:7)PA13_22") (pintype "bidirectional"))
      (node (ref "IC2") (pin "6") (pinfunction "SCL_6") (pintype "bidirectional"))
      (node (ref "R16") (pin "1") (pinfunction "1_1") (pintype "passive"))
      (node (ref "U1") (pin "9") (pinfunction "SCX_9") (pintype "bidirectional"))
    )
    (net (code "9") (name "IMU_SDA") (class "Default")
      (node (ref "IC1") (pin "21") (pinfunction "(SDA/S2:0|4:0/T2:0|0:6)PA12_21") (pintype "bidirectional"))
      (node (ref "IC2") (pin "5") (pinfunction "SDA_5") (pintype "bidirectional"))
      (node (ref "R34") (pin "1") (pinfunction "1_1") (pintype "passive"))
      (node (ref "U1") (pin "11") (pinfunction "SDX_11") (pintype "bidirectional"))
    )
    (net (code "10") (name "MCU_CS_SD") (class "Default")
      (node (ref "IC1") (pin "23") (pinfunction "(XIN/S2:2|4:2/T3:0|0:4)PA14_23") (pintype "bidirectional"))
      (node (ref "IC5") (pin "1") (pinfunction "G_1") (pintype "input"))
      (node (ref "IC5") (pin "2") (pinfunction "A1_2") (pintype "input"))
      (node (ref "R15") (pin "1") (pinfunction "1_1") (pintype "passive"))
    )
    (net (code "11") (name "MCU_CS_XBEE1") (class "Default")
      (node (ref "IC1") (pin "27") (pinfunction "(S1:2|3:2/T3:0|0:2)PA18_27") (pintype "bidirectional"))
      (node (ref "IC3") (pin "1") (pinfunction "G_1") (pintype "input"))
      (node (ref "IC3") (pin "2") (pinfunction "A1_2") (pintype "input"))
    )
    (net (code "12") (name "MCU_CS_XBEE2") (class "Default")
      (node (ref "IC1") (pin "29") (pinfunction "(S5:2|3:2/T7:0|0:6)PA20_29") (pintype "bidirectional"))
      (node (ref "IC5") (pin "17") (pinfunction "A4_17") (pintype "input"))
      (node (ref "IC5") (pin "19") (pinfunction "G_19") (pintype "input"))
    )
    (net (code "13") (name "MCU_IRQ_XBEE1") (class "Default")
      (node (ref "IC1") (pin "30") (pinfunction "(S5:3|3:3/T7:1|0:7)PA21_30") (pintype "bidirectional"))
      (node (ref "R13") (pin "2") (pinfunction "2_2") (pintype "passive"))
    )
    (net (code "14") (name "MCU_IRQ_XBEE2") (class "Default")
      (node (ref "IC1") (pin "24") (pinfunction "(XOUT/S2:3|4:3/T3:1|0:5)PA15_24") (pintype "bidirectional"))
      (node (ref "R18") (pin "2") (pinfunction "2_2") (pintype "passive"))
    )
    (net (code "15") (name "MCU_MISO") (class "Default")
      (node (ref "IC1") (pin "28") (pinfunction "(S1:3|3:3/T3:1|0:3)PA19_28") (pintype "bidirectional"))
      (node (ref "IC3") (pin "12") (pinfunction "Y4_12") (pintype "tri_state"))
      (node (ref "IC5") (pin "12") (pinfunction "Y4_12") (pintype "tri_state"))
      (node (ref "IC5") (pin "9") (pinfunction "Y1_9") (pintype "tri_state"))
    )
    (net (code "16") (name "MCU_MOSI") (class "Default")
      (node (ref "IC1") (pin "25") (pinfunction "(SDA/S1:0|3:0/T2:0|0:6)PA16_25") (pintype "bidirectional"))
      (node (ref "IC3") (pin "4") (pinfunction "A2_4") (pintype "input"))
      (node (ref "IC5") (pin "13") (pinfunction "A2_13") (pintype "input"))
      (node (ref "IC5") (pin "4") (pinfunction "A2_4") (pintype "input"))
    )
    (net (code "17") (name "MCU_RX1") (class "Default")
      (node (ref "IC1") (pin "32") (pinfunction "(SCL/S3:1|5:1/T4:1|0:5)PA23_32") (pintype "bidirectional"))
      (node (ref "IC3") (pin "7") (pinfunction "Y2_7") (pintype "tri_state"))
    )
    (net (code "18") (name "MCU_RX2") (class "Default")
      (node (ref "IC1") (pin "8") (pinfunction "(S4:1/T4:1/AIN2)PB09_8") (pintype "bidirectional"))
      (node (ref "IC3") (pin "3") (pinfunction "Y4_3") (pintype "tri_state"))
    )
    (net (code "19") (name "MCU_RX_XBEE1") (class "Default")
      (node (ref "IC1") (pin "38") (pinfunction "(S5:3/T7:1)PB23_38") (pintype "bidirectional"))
      (node (ref "R11") (pin "1") (pinfunction "1_1") (pintype "passive"))
    )
    (net (code "20") (name "MCU_RX_XBEE2") (class "Default")
      (node (ref "IC1") (pin "16") (pinfunction "(S0:3|2:3/T1:1|0:3/AIN19)PA11_16") (pintype "bidirectional"))
      (node (ref "R21") (pin "1") (pinfunction "1_1") (pintype "passive"))
    )
    (net (code "21") (name "MCU_SCK") (class "Default")
      (node (ref "IC1") (pin "26") (pinfunction "(SCL/S1:1|3:1/T2:1|0:7)PA17_26") (pintype "bidirectional"))
      (node (ref "IC3") (pin "6") (pinfunction "A3_6") (pintype "input"))
      (node (ref "IC5") (pin "15") (pinfunction "A3_15") (pintype "input"))
      (node (ref "IC5") (pin "6") (pinfunction "A3_6") (pintype "input"))
    )
    (net (code "22") (name "MCU_SCL") (class "Default")
      (node (ref "IC1") (pin "14") (pinfunction "(SCL/S0:1|2:1/T0:1|1:3/AIN17)PA09_14") (pintype "bidirectional"))
      (node (ref "R3") (pin "1") (pinfunction "1_1") (pintype "passive"))
      (node (ref "T5") (pin "1") (pinfunction "S_1") (pintype "passive"))
    )
    (net (code "23") (name "MCU_SDA") (class "Default")
      (node (ref "IC1") (pin "13") (pinfunction "(SDA/S0:0|2:0/T0:0|1:2/AIN16)PA08_13") (pintype "bidirectional"))
      (node (ref "R5") (pin "1") (pinfunction "1_1") (pintype "passive"))
      (node (ref "T5") (pin "4") (pinfunction "S_4") (pintype "passive"))
    )
    (net (code "24") (name "MCU_TX1") (class "Default")
      (node (ref "IC1") (pin "31") (pinfunction "(SDA/S3:0|5:0/T4:0|0:4)PA22_31") (pintype "bidirectional"))
      (node (ref "IC3") (pin "11") (pinfunction "A1_11") (pintype "input"))
    )
    (net (code "25") (name "MCU_TX2") (class "Default")
      (node (ref "IC1") (pin "7") (pinfunction "(S4:0/T4:0/AIN2)PB08_7") (pintype "bidirectional"))
      (node (ref "IC3") (pin "15") (pinfunction "A3_15") (pintype "input"))
    )
    (net (code "26") (name "MCU_TX_XBEE1") (class "Default")
      (node (ref "IC1") (pin "37") (pinfunction "(S5:2/T7:0)PB22_37") (pintype "bidirectional"))
      (node (ref "R12") (pin "1") (pinfunction "1_1") (pintype "passive"))
    )
    (net (code "27") (name "MCU_TX_XBEE2") (class "Default")
      (node (ref "IC1") (pin "15") (pinfunction "(S0:2|2:2/T1:0|0:2/AIN18)PA10_15") (pintype "bidirectional"))
      (node (ref "R20") (pin "1") (pinfunction "1_1") (pintype "passive"))
    )
    (net (code "28") (name "Net-(D3-PadA)") (class "Default")
      (node (ref "D3") (pin "A") (pinfunction "A_A") (pintype "passive"))
      (node (ref "D4") (pin "C") (pinfunction "C_C") (pintype "passive"))
      (node (ref "R22") (pin "2") (pinfunction "2_2") (pintype "passive"))
    )
    (net (code "29") (name "Net-(D5-PadA)") (class "Default")
      (node (ref "D5") (pin "A") (pinfunction "A_A") (pintype "passive"))
      (node (ref "R28") (pin "1") (pinfunction "1_1") (pintype "passive"))
    )
    (net (code "30") (name "Net-(D6-PadA)") (class "Default")
      (node (ref "D6") (pin "A") (pinfunction "A_A") (pintype "passive"))
      (node (ref "R29") (pin "1") (pinfunction "1_1") (pintype "passive"))
    )
    (net (code "31") (name "Net-(D7-PadA)") (class "Default")
      (node (ref "D7") (pin "A") (pinfunction "A_A") (pintype "passive"))
      (node (ref "R30") (pin "1") (pinfunction "1_1") (pintype "passive"))
    )
    (net (code "32") (name "Net-(D8-PadA)") (class "Default")
      (node (ref "D8") (pin "A") (pinfunction "A_A") (pintype "passive"))
      (node (ref "R31") (pin "1") (pinfunction "1_1") (pintype "passive"))
    )
    (net (code "33") (name "Net-(D9-PadA)") (class "Default")
      (node (ref "D9") (pin "A") (pinfunction "A_A") (pintype "passive"))
      (node (ref "R32") (pin "1") (pinfunction "1_1") (pintype "passive"))
    )
    (net (code "34") (name "Net-(F1-Pad1)") (class "Default")
      (node (ref "F1") (pin "1") (pinfunction "1_1") (pintype "passive"))
      (node (ref "USB") (pin "VBUS") (pinfunction "VBUS_VBUS") (pintype "power_in"))
    )
    (net (code "35") (name "Net-(IC1-(XIN32{slash}S1:0{slash}T2:0)PA00)") (class "Default")
      (node (ref "C3") (pin "1") (pinfunction "1_1") (pintype "passive"))
      (node (ref "IC1") (pin "1") (pinfunction "(XIN32/S1:0/T2:0)PA00_1") (pintype "bidirectional"))
      (node (ref "Q1") (pin "2") (pinfunction "2_2") (pintype "passive"))
    )
    (net (code "36") (name "Net-(IC1-(XOUT32{slash}S1:1{slash}T2:1)PA01)") (class "Default")
      (node (ref "C4") (pin "2") (pinfunction "2_2") (pintype "passive"))
      (node (ref "IC1") (pin "2") (pinfunction "(XOUT32/S1:1/T2:1)PA01_2") (pintype "bidirectional"))
      (node (ref "Q1") (pin "1") (pinfunction "1_1") (pintype "passive"))
    )
    (net (code "37") (name "Net-(IC1-VCCCORE)") (class "Default")
      (node (ref "C21") (pin "2") (pinfunction "2_2") (pintype "passive"))
      (node (ref "IC1") (pin "43") (pinfunction "VCCCORE_43") (pintype "power_in"))
    )
    (net (code "38") (name "Net-(R14-Pad2)") (class "Default")
      (node (ref "R14") (pin "2") (pinfunction "2_2") (pintype "passive"))
      (node (ref "USB") (pin "SHLD1") (pinfunction "SHIELD_SHLD1") (pintype "passive"))
      (node (ref "USB") (pin "SHLD2") (pinfunction "SHIELD_SHLD2") (pintype "passive"))
      (node (ref "USB") (pin "SHLD3") (pinfunction "SHIELD_SHLD3") (pintype "passive"))
      (node (ref "USB") (pin "SHLD4") (pinfunction "SHIELD_SHLD4") (pintype "passive"))
      (node (ref "USB") (pin "SHLD5") (pinfunction "SHIELD_SHLD5") (pintype "passive"))
      (node (ref "USB") (pin "SHLD6") (pinfunction "SHIELD_SHLD6") (pintype "passive"))
      (node (ref "USB") (pin "SHLD7") (pinfunction "SHIELD_SHLD7") (pintype "passive"))
      (node (ref "USB") (pin "SHLD8") (pinfunction "SHIELD_SHLD8") (pintype "passive"))
    )
    (net (code "39") (name "Net-(R25-Pad2)") (class "Default")
      (node (ref "R25") (pin "2") (pinfunction "2_2") (pintype "passive"))
      (node (ref "RESET") (pin "3") (pinfunction "S1_3") (pintype "passive"))
      (node (ref "RESET") (pin "4") (pinfunction "S1_4") (pintype "passive"))
    )
    (net (code "40") (name "Net-(T2-G)") (class "Default")
      (node (ref "R8") (pin "2") (pinfunction "2_2") (pintype "passive"))
      (node (ref "T2") (pin "1") (pinfunction "G_1") (pintype "passive"))
      (node (ref "T4") (pin "6") (pinfunction "D_6") (pintype "passive"))
    )
    (net (code "41") (name "Net-(XBEE1-~{RESET})") (class "Default")
      (node (ref "R10") (pin "2") (pinfunction "2_2") (pintype "passive"))
      (node (ref "XBEE1") (pin "5") (pinfunction "~{RESET}_5") (pintype "bidirectional"))
    )
    (net (code "42") (name "Net-(XBEE2-~{RESET})") (class "Default")
      (node (ref "R19") (pin "2") (pinfunction "2_2") (pintype "passive"))
      (node (ref "XBEE2") (pin "5") (pinfunction "~{RESET}_5") (pintype "bidirectional"))
    )
    (net (code "43") (name "RST") (class "Default")
      (node (ref "C1") (pin "2") (pinfunction "2_2") (pintype "passive"))
      (node (ref "IC1") (pin "40") (pinfunction "~{RESET}_40") (pintype "input"))
      (node (ref "R24") (pin "2") (pinfunction "2_2") (pintype "passive"))
      (node (ref "R25") (pin "1") (pinfunction "1_1") (pintype "passive"))
      (node (ref "SWD") (pin "RST") (pinfunction "RST_RST") (pintype "bidirectional"))
    )
    (net (code "44") (name "SDO1") (class "Default")
      (node (ref "R35") (pin "1") (pinfunction "1_1") (pintype "passive"))
      (node (ref "R37") (pin "2") (pinfunction "2_2") (pintype "passive"))
      (node (ref "U1") (pin "17") (pinfunction "SDO1_17") (pintype "bidirectional"))
    )
    (net (code "45") (name "SDO2") (class "Default")
      (node (ref "R36") (pin "1") (pinfunction "1_1") (pintype "passive"))
      (node (ref "R38") (pin "2") (pinfunction "2_2") (pintype "passive"))
      (node (ref "U1") (pin "12") (pinfunction "SDO2_12") (pintype "bidirectional"))
    )
    (net (code "46") (name "SD_CS") (class "Default")
      (node (ref "IC5") (pin "18") (pinfunction "Y1_18") (pintype "tri_state"))
      (node (ref "R1") (pin "2") (pinfunction "2_2") (pintype "passive"))
      (node (ref "SD") (pin "CS") (pinfunction "~{CS}_CS") (pintype "bidirectional"))
    )
    (net (code "47") (name "SD_MISO") (class "Default")
      (node (ref "IC5") (pin "8") (pinfunction "A4_8") (pintype "input"))
      (node (ref "SD") (pin "MISO") (pinfunction "MISO_MISO") (pintype "bidirectional"))
    )
    (net (code "48") (name "SD_MOSI") (class "Default")
      (node (ref "IC5") (pin "16") (pinfunction "Y2_16") (pintype "tri_state"))
      (node (ref "SD") (pin "MOSI") (pinfunction "MOSI_MOSI") (pintype "bidirectional"))
    )
    (net (code "49") (name "SD_SCK") (class "Default")
      (node (ref "IC5") (pin "14") (pinfunction "Y3_14") (pintype "tri_state"))
      (node (ref "SD") (pin "SCK") (pinfunction "SCK_SCK") (pintype "bidirectional"))
    )
    (net (code "50") (name "SD_VCC") (class "Default")
      (node (ref "C5") (pin "2") (pinfunction "2_2") (pintype "passive"))
      (node (ref "C6") (pin "2") (pinfunction "2_2") (pintype "passive"))
      (node (ref "R1") (pin "1") (pinfunction "1_1") (pintype "passive"))
      (node (ref "R30") (pin "2") (pinfunction "2_2") (pintype "passive"))
      (node (ref "SD") (pin "VCC") (pinfunction "3V3_VCC") (pintype "bidirectional"))
      (node (ref "T1") (pin "3") (pinfunction "D_3") (pintype "passive"))
    )
    (net (code "51") (name "STATUS_LED1") (class "Default")
      (node (ref "IC1") (pin "39") (pinfunction "PA27_39") (pintype "bidirectional"))
      (node (ref "R22") (pin "1") (pinfunction "1_1") (pintype "passive"))
    )
    (net (code "52") (name "STATUS_LED2") (class "Default")
      (node (ref "D3") (pin "C") (pinfunction "C_C") (pintype "passive"))
      (node (ref "D4") (pin "A") (pinfunction "A_A") (pintype "passive"))
      (node (ref "IC1") (pin "41") (pinfunction "PA28_41") (pintype "bidirectional"))
    )
    (net (code "53") (name "SWCLK") (class "Default")
      (node (ref "IC1") (pin "45") (pinfunction "(SWCLK/S1:2/T1:0)PA30_45") (pintype "bidirectional"))
      (node (ref "R33") (pin "2") (pinfunction "2_2") (pintype "passive"))
      (node (ref "SWD") (pin "SWCLK") (pinfunction "SWCLK_SWCLK") (pintype "bidirectional"))
    )
    (net (code "54") (name "SWDIO") (class "Default")
      (node (ref "IC1") (pin "46") (pinfunction "(SWDIO/S1:3/T1:1)PA31_46") (pintype "bidirectional"))
      (node (ref "SWD") (pin "SWDIO") (pinfunction "SWDIO_SWDIO") (pintype "bidirectional"))
    )
    (net (code "55") (name "UART_CS") (class "Default")
      (node (ref "IC3") (pin "19") (pinfunction "G_19") (pintype "input"))
      (node (ref "R9") (pin "2") (pinfunction "2_2") (pintype "passive"))
      (node (ref "T3") (pin "1") (pinfunction "G_1") (pintype "passive"))
      (node (ref "T4") (pin "3") (pinfunction "D_3") (pintype "passive"))
    )
    (net (code "56") (name "UART_PWR") (class "Default")
      (node (ref "IC1") (pin "11") (pinfunction "(S0:2/T1:0/AIN6)PA06_11") (pintype "bidirectional"))
      (node (ref "R27") (pin "1") (pinfunction "1_1") (pintype "passive"))
      (node (ref "T4") (pin "5") (pinfunction "G_5") (pintype "passive"))
    )
    (net (code "57") (name "UART_RX1") (class "Default")
      (node (ref "IC3") (pin "13") (pinfunction "A2_13") (pintype "input"))
      (node (ref "J7") (pin "4") (pinfunction "4_4") (pintype "passive"))
    )
    (net (code "58") (name "UART_RX2") (class "Default")
      (node (ref "IC3") (pin "17") (pinfunction "A4_17") (pintype "input"))
      (node (ref "J8") (pin "4") (pinfunction "4_4") (pintype "passive"))
    )
    (net (code "59") (name "UART_TX1") (class "Default")
      (node (ref "IC3") (pin "9") (pinfunction "Y1_9") (pintype "tri_state"))
      (node (ref "J7") (pin "3") (pinfunction "3_3") (pintype "passive"))
    )
    (net (code "60") (name "UART_TX2") (class "Default")
      (node (ref "IC3") (pin "5") (pinfunction "Y3_5") (pintype "tri_state"))
      (node (ref "J8") (pin "3") (pinfunction "3_3") (pintype "passive"))
    )
    (net (code "61") (name "UART_VCC") (class "Default")
      (node (ref "J7") (pin "2") (pinfunction "2_2") (pintype "passive"))
      (node (ref "J8") (pin "2") (pinfunction "2_2") (pintype "passive"))
      (node (ref "R32") (pin "2") (pinfunction "2_2") (pintype "passive"))
      (node (ref "T3") (pin "3") (pinfunction "D_3") (pintype "passive"))
    )
    (net (code "62") (name "USB_D+") (class "Default")
      (node (ref "D1") (pin "2") (pinfunction "C2_2") (pintype "passive"))
      (node (ref "IC1") (pin "34") (pinfunction "(USB_DP/S3:3|5:3/T5:1|1:3)PA25_34") (pintype "bidirectional"))
      (node (ref "USB") (pin "D+") (pinfunction "D+_D+") (pintype "bidirectional"))
    )
    (net (code "63") (name "USB_D-") (class "Default")
      (node (ref "D1") (pin "1") (pinfunction "C1_1") (pintype "passive"))
      (node (ref "IC1") (pin "33") (pinfunction "(USB_DM/S3:2|5:2/T5:0|1:2)PA24_33") (pintype "bidirectional"))
      (node (ref "USB") (pin "D-") (pinfunction "D-_D-") (pintype "bidirectional"))
    )
    (net (code "64") (name "VCCANA") (class "Default")
      (node (ref "C16") (pin "2") (pinfunction "2_2") (pintype "passive"))
      (node (ref "C22") (pin "2") (pinfunction "2_2") (pintype "passive"))
      (node (ref "IC1") (pin "6") (pinfunction "VCCANA_6") (pintype "power_in"))
      (node (ref "R23") (pin "2") (pinfunction "2_2") (pintype "passive"))
    )
    (net (code "65") (name "XBEE1_CS") (class "Default")
      (node (ref "IC3") (pin "18") (pinfunction "Y1_18") (pintype "tri_state"))
      (node (ref "XBEE1") (pin "17") (pinfunction "AD3/DIO3/SS_17") (pintype "bidirectional"))
    )
    (net (code "66") (name "XBEE1_CTS{slash}IRQ") (class "Default")
      (node (ref "R13") (pin "1") (pinfunction "1_1") (pintype "passive"))
      (node (ref "XBEE1") (pin "12") (pinfunction "DIO7/CTS_12") (pintype "bidirectional"))
    )
    (net (code "67") (name "XBEE1_MISO") (class "Default")
      (node (ref "IC3") (pin "8") (pinfunction "A4_8") (pintype "input"))
      (node (ref "XBEE1") (pin "4") (pinfunction "MISO/DIO12_4") (pintype "bidirectional"))
    )
    (net (code "68") (name "XBEE1_MOSI") (class "Default")
      (node (ref "IC3") (pin "16") (pinfunction "Y2_16") (pintype "tri_state"))
      (node (ref "XBEE1") (pin "11") (pinfunction "DIO4/MOSI_11") (pintype "bidirectional"))
    )
    (net (code "69") (name "XBEE1_RX") (class "Default")
      (node (ref "R12") (pin "2") (pinfunction "2_2") (pintype "passive"))
      (node (ref "XBEE1") (pin "3") (pinfunction "DIN/RX/~{CFG}_3") (pintype "bidirectional"))
    )
    (net (code "70") (name "XBEE1_SCK") (class "Default")
      (node (ref "IC3") (pin "14") (pinfunction "Y3_14") (pintype "tri_state"))
      (node (ref "XBEE1") (pin "18") (pinfunction "AD2/DIO2/SCK_18") (pintype "bidirectional"))
    )
    (net (code "71") (name "XBEE1_TX") (class "Default")
      (node (ref "R11") (pin "2") (pinfunction "2_2") (pintype "passive"))
      (node (ref "XBEE1") (pin "2") (pinfunction "DOUT/TX_2") (pintype "bidirectional"))
    )
    (net (code "72") (name "XBEE1_VCC") (class "Default")
      (node (ref "C14") (pin "2") (pinfunction "2_2") (pintype "passive"))
      (node (ref "C15") (pin "2") (pinfunction "2_2") (pintype "passive"))
      (node (ref "C2") (pin "2") (pinfunction "2_2") (pintype "passive"))
      (node (ref "R10") (pin "1") (pinfunction "1_1") (pintype "passive"))
      (node (ref "R28") (pin "2") (pinfunction "2_2") (pintype "passive"))
      (node (ref "T7") (pin "3") (pinfunction "D_3") (pintype "passive"))
      (node (ref "XBEE1") (pin "1") (pinfunction "VCC_1") (pintype "power_in"))
    )
    (net (code "73") (name "XBEE2_CS") (class "Default")
      (node (ref "IC5") (pin "3") (pinfunction "Y4_3") (pintype "tri_state"))
      (node (ref "XBEE2") (pin "17") (pinfunction "AD3/DIO3/SS_17") (pintype "bidirectional"))
    )
    (net (code "74") (name "XBEE2_CTS{slash}IRQ") (class "Default")
      (node (ref "R18") (pin "1") (pinfunction "1_1") (pintype "passive"))
      (node (ref "XBEE2") (pin "12") (pinfunction "DIO7/CTS_12") (pintype "bidirectional"))
    )
    (net (code "75") (name "XBEE2_MISO") (class "Default")
      (node (ref "IC5") (pin "11") (pinfunction "A1_11") (pintype "input"))
      (node (ref "XBEE2") (pin "4") (pinfunction "MISO/DIO12_4") (pintype "bidirectional"))
    )
    (net (code "76") (name "XBEE2_MOSI") (class "Default")
      (node (ref "IC5") (pin "7") (pinfunction "Y2_7") (pintype "tri_state"))
      (node (ref "XBEE2") (pin "11") (pinfunction "DIO4/MOSI_11") (pintype "bidirectional"))
    )
    (net (code "77") (name "XBEE2_RX") (class "Default")
      (node (ref "R20") (pin "2") (pinfunction "2_2") (pintype "passive"))
      (node (ref "XBEE2") (pin "3") (pinfunction "DIN/RX/~{CFG}_3") (pintype "bidirectional"))
    )
    (net (code "78") (name "XBEE2_SCK") (class "Default")
      (node (ref "IC5") (pin "5") (pinfunction "Y3_5") (pintype "tri_state"))
      (node (ref "XBEE2") (pin "18") (pinfunction "AD2/DIO2/SCK_18") (pintype "bidirectional"))
    )
    (net (code "79") (name "XBEE2_TX") (class "Default")
      (node (ref "R21") (pin "2") (pinfunction "2_2") (pintype "passive"))
      (node (ref "XBEE2") (pin "2") (pinfunction "DOUT/TX_2") (pintype "bidirectional"))
    )
    (net (code "80") (name "XBEE2_VCC") (class "Default")
      (node (ref "C17") (pin "2") (pinfunction "2_2") (pintype "passive"))
      (node (ref "C18") (pin "2") (pinfunction "2_2") (pintype "passive"))
      (node (ref "C19") (pin "2") (pinfunction "2_2") (pintype "passive"))
      (node (ref "R19") (pin "1") (pinfunction "1_1") (pintype "passive"))
      (node (ref "R29") (pin "2") (pinfunction "2_2") (pintype "passive"))
      (node (ref "T6") (pin "3") (pinfunction "D_3") (pintype "passive"))
      (node (ref "XBEE2") (pin "1") (pinfunction "VCC_1") (pintype "power_in"))
    )
    (net (code "81") (name "unconnected-(IC1-(DAC{slash}AIN0)PA02-Pad3)") (class "Default")
      (node (ref "IC1") (pin "3") (pinfunction "(DAC/AIN0)PA02_3") (pintype "bidirectional"))
    )
    (net (code "82") (name "unconnected-(IC1-(REFA{slash}AIN1)PA03-Pad4)") (class "Default")
      (node (ref "IC1") (pin "4") (pinfunction "(REFA/AIN1)PA03_4") (pintype "bidirectional"))
    )
    (net (code "83") (name "unconnected-(IC1-(S0:0{slash}T0:0{slash}REFB{slash}AIN4)PA04-Pad9)") (class "Default")
      (node (ref "IC1") (pin "9") (pinfunction "(S0:0/T0:0/REFB/AIN4)PA04_9") (pintype "bidirectional"))
    )
    (net (code "84") (name "unconnected-(IC1-(S5:0{slash}T6:0{slash}AIN10)PB02-Pad47)") (class "Default")
      (node (ref "IC1") (pin "47") (pinfunction "(S5:0/T6:0/AIN10)PB02_47") (pintype "bidirectional"))
    )
    (net (code "85") (name "unconnected-(IC1-(S:1{slash}T6:1{slash}AIN11)PB03-Pad48)") (class "Default")
      (node (ref "IC1") (pin "48") (pinfunction "(S:1/T6:1/AIN11)PB03_48") (pintype "bidirectional"))
    )
    (net (code "86") (name "unconnected-(SD-PadDAT1)") (class "Default")
      (node (ref "SD") (pin "DAT1") (pinfunction "DAT1_DAT1") (pintype "bidirectional"))
    )
    (net (code "87") (name "unconnected-(SD-PadDAT2)") (class "Default")
      (node (ref "SD") (pin "DAT2") (pinfunction "DAT2_DAT2") (pintype "bidirectional"))
    )
    (net (code "88") (name "unconnected-(U1-CSB1-Pad16)") (class "Default")
      (node (ref "U1") (pin "16") (pinfunction "CSB1_16") (pintype "bidirectional"))
    )
    (net (code "89") (name "unconnected-(U1-CSB2-Pad5)") (class "Default")
      (node (ref "U1") (pin "5") (pinfunction "CSB2_5") (pintype "bidirectional"))
    )
    (net (code "90") (name "unconnected-(U1-CSB3-Pad20)") (class "Default")
      (node (ref "U1") (pin "20") (pinfunction "CSB3_20") (pintype "bidirectional"))
    )
    (net (code "91") (name "unconnected-(U1-DRDYM-Pad2)") (class "Default")
      (node (ref "U1") (pin "2") (pinfunction "DRDYM_2") (pintype "bidirectional"))
    )
    (net (code "92") (name "unconnected-(U1-INT1-Pad19)") (class "Default")
      (node (ref "U1") (pin "19") (pinfunction "INT1_19") (pintype "bidirectional"))
    )
    (net (code "93") (name "unconnected-(U1-INT2-Pad1)") (class "Default")
      (node (ref "U1") (pin "1") (pinfunction "INT2_1") (pintype "input"))
    )
    (net (code "94") (name "unconnected-(U1-INT3-Pad14)") (class "Default")
      (node (ref "U1") (pin "14") (pinfunction "INT3_14") (pintype "bidirectional"))
    )
    (net (code "95") (name "unconnected-(U1-INT4-Pad15)") (class "Default")
      (node (ref "U1") (pin "15") (pinfunction "INT4_15") (pintype "bidirectional"))
    )
    (net (code "96") (name "unconnected-(U1-INT5-Pad10)") (class "Default")
      (node (ref "U1") (pin "10") (pinfunction "INT5_10") (pintype "output"))
    )
    (net (code "97") (name "unconnected-(XBEE1-AD0{slash}DIO0{slash}SDA{slash}CB-Pad20)") (class "Default")
      (node (ref "XBEE1") (pin "20") (pinfunction "AD0/DIO0/SDA/CB_20") (pintype "bidirectional"))
    )
    (net (code "98") (name "unconnected-(XBEE1-AD1{slash}DIO1{slash}SCL{slash}ATTN-Pad19)") (class "Default")
      (node (ref "XBEE1") (pin "19") (pinfunction "AD1/DIO1/SCL/ATTN_19") (pintype "bidirectional"))
    )
    (net (code "99") (name "unconnected-(XBEE1-DIO5{slash}ASSC-Pad15)") (class "Default")
      (node (ref "XBEE1") (pin "15") (pinfunction "DIO5/ASSC_15") (pintype "bidirectional"))
    )
    (net (code "100") (name "unconnected-(XBEE1-DIO6{slash}RTS-Pad16)") (class "Default")
      (node (ref "XBEE1") (pin "16") (pinfunction "DIO6/RTS_16") (pintype "bidirectional"))
    )
    (net (code "101") (name "unconnected-(XBEE1-DIO9{slash}ON_~{SLEEP}-Pad13)") (class "Default")
      (node (ref "XBEE1") (pin "13") (pinfunction "DIO9/ON_~{SLEEP}_13") (pintype "bidirectional"))
    )
    (net (code "102") (name "unconnected-(XBEE1-DTR{slash}DIO8-Pad9)") (class "Default")
      (node (ref "XBEE1") (pin "9") (pinfunction "DTR/DIO8_9") (pintype "bidirectional"))
    )
    (net (code "103") (name "unconnected-(XBEE1-PWM1{slash}DIO11-Pad7)") (class "Default")
      (node (ref "XBEE1") (pin "7") (pinfunction "PWM1/DIO11_7") (pintype "bidirectional"))
    )
    (net (code "104") (name "unconnected-(XBEE1-RES-Pad8)") (class "Default")
      (node (ref "XBEE1") (pin "8") (pinfunction "RES_8") (pintype "bidirectional"))
    )
    (net (code "105") (name "unconnected-(XBEE1-RSSI{slash}PWM0{slash}DIO10-Pad6)") (class "Default")
      (node (ref "XBEE1") (pin "6") (pinfunction "RSSI/PWM0/DIO10_6") (pintype "bidirectional"))
    )
    (net (code "106") (name "unconnected-(XBEE1-VREF-Pad14)") (class "Default")
      (node (ref "XBEE1") (pin "14") (pinfunction "VREF_14") (pintype "bidirectional"))
    )
    (net (code "107") (name "unconnected-(XBEE2-AD0{slash}DIO0{slash}SDA{slash}CB-Pad20)") (class "Default")
      (node (ref "XBEE2") (pin "20") (pinfunction "AD0/DIO0/SDA/CB_20") (pintype "bidirectional"))
    )
    (net (code "108") (name "unconnected-(XBEE2-AD1{slash}DIO1{slash}SCL{slash}ATTN-Pad19)") (class "Default")
      (node (ref "XBEE2") (pin "19") (pinfunction "AD1/DIO1/SCL/ATTN_19") (pintype "bidirectional"))
    )
    (net (code "109") (name "unconnected-(XBEE2-DIO5{slash}ASSC-Pad15)") (class "Default")
      (node (ref "XBEE2") (pin "15") (pinfunction "DIO5/ASSC_15") (pintype "bidirectional"))
    )
    (net (code "110") (name "unconnected-(XBEE2-DIO6{slash}RTS-Pad16)") (class "Default")
      (node (ref "XBEE2") (pin "16") (pinfunction "DIO6/RTS_16") (pintype "bidirectional"))
    )
    (net (code "111") (name "unconnected-(XBEE2-DIO9{slash}ON_~{SLEEP}-Pad13)") (class "Default")
      (node (ref "XBEE2") (pin "13") (pinfunction "DIO9/ON_~{SLEEP}_13") (pintype "bidirectional"))
    )
    (net (code "112") (name "unconnected-(XBEE2-DTR{slash}DIO8-Pad9)") (class "Default")
      (node (ref "XBEE2") (pin "9") (pinfunction "DTR/DIO8_9") (pintype "bidirectional"))
    )
    (net (code "113") (name "unconnected-(XBEE2-PWM1{slash}DIO11-Pad7)") (class "Default")
      (node (ref "XBEE2") (pin "7") (pinfunction "PWM1/DIO11_7") (pintype "bidirectional"))
    )
    (net (code "114") (name "unconnected-(XBEE2-RES-Pad8)") (class "Default")
      (node (ref "XBEE2") (pin "8") (pinfunction "RES_8") (pintype "bidirectional"))
    )
    (net (code "115") (name "unconnected-(XBEE2-RSSI{slash}PWM0{slash}DIO10-Pad6)") (class "Default")
      (node (ref "XBEE2") (pin "6") (pinfunction "RSSI/PWM0/DIO10_6") (pintype "bidirectional"))
    )
    (net (code "116") (name "unconnected-(XBEE2-VREF-Pad14)") (class "Default")
      (node (ref "XBEE2") (pin "14") (pinfunction "VREF_14") (pintype "bidirectional"))
    )
    (net (code "117") (name "~{SD_PWR}") (class "Default")
      (node (ref "IC1") (pin "12") (pinfunction "(S0:3/T1:1/AIN7)PA07_12") (pintype "bidirectional"))
      (node (ref "R2") (pin "2") (pinfunction "2_2") (pintype "passive"))
      (node (ref "T1") (pin "1") (pinfunction "G_1") (pintype "passive"))
    )
    (net (code "118") (name "~{XBEE1_PWR}") (class "Default")
      (node (ref "IC1") (pin "20") (pinfunction "(S4:3/T5:1|0:5)PB11_20") (pintype "bidirectional"))
      (node (ref "R6") (pin "2") (pinfunction "2_2") (pintype "passive"))
      (node (ref "T7") (pin "1") (pinfunction "G_1") (pintype "passive"))
    )
    (net (code "119") (name "~{XBEE2_PWR}") (class "Default")
      (node (ref "IC1") (pin "19") (pinfunction "(S4:2/T5:0|0:4)PB10_19") (pintype "bidirectional"))
      (node (ref "R17") (pin "2") (pinfunction "2_2") (pintype "passive"))
      (node (ref "T6") (pin "1") (pinfunction "G_1") (pintype "passive"))
    )
  )
)
